# FPGA_RAM.net
KiCad netlist of a schematic drawn in Altium Designer
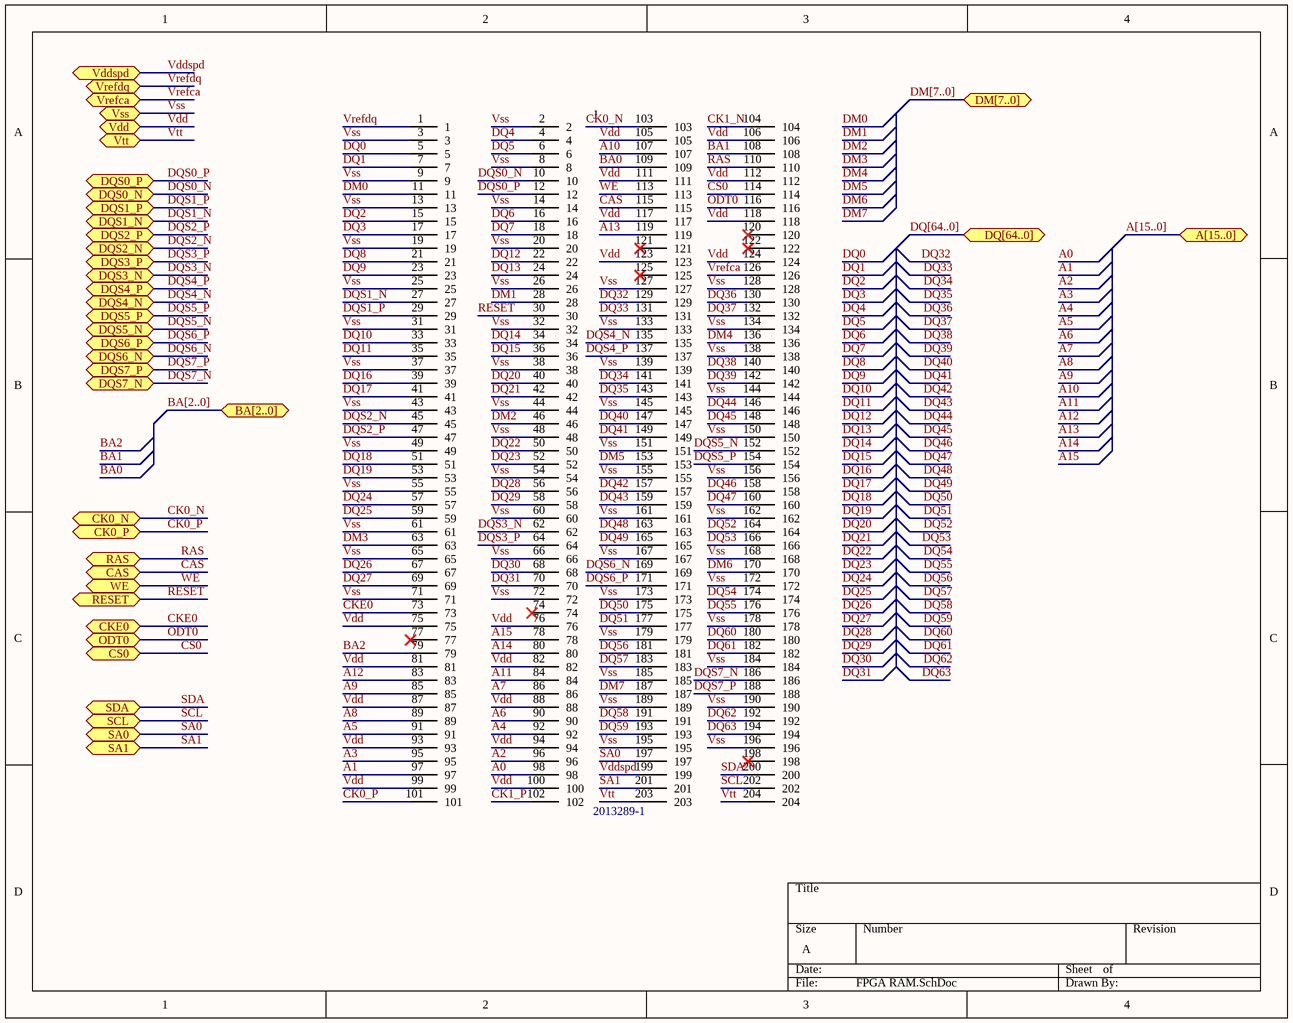
[diagram p0: FPGA RAM.SchDoc]

(export (version "E")
  (design (tool "Eeschema 10.0.6"))
  (components
    (comp (ref "J")
      (value "2013289-1")
      (footprint "2020-09-26_17-27-19:TE_2013289-1")
      (description "204 Position 0.6 mm Pitch Right Angle Surface Mount Socket DIMM Connector")
      (fields (field (name "DIGI-KEY_PART_NUMBER") "A115021-ND") (field (name "MF") "TE Connectivity"))
      (libsource (lib "2020-09-26_17-27-19") (part "2013289-1"))
    )
  )
  (nets
    (net (code "2") (name "/A0") (class "Default")
      (node (ref "J") (pin "98") (pinfunction "98_98") (pintype "passive"))
    )
    (net (code "3") (name "/A1") (class "Default")
      (node (ref "J") (pin "97") (pinfunction "97_97") (pintype "passive"))
    )
    (net (code "4") (name "/A2") (class "Default")
      (node (ref "J") (pin "96") (pinfunction "96_96") (pintype "passive"))
    )
    (net (code "5") (name "/A3") (class "Default")
      (node (ref "J") (pin "95") (pinfunction "95_95") (pintype "passive"))
    )
    (net (code "6") (name "/A4") (class "Default")
      (node (ref "J") (pin "92") (pinfunction "92_92") (pintype "passive"))
    )
    (net (code "7") (name "/A5") (class "Default")
      (node (ref "J") (pin "91") (pinfunction "91_91") (pintype "passive"))
    )
    (net (code "8") (name "/A6") (class "Default")
      (node (ref "J") (pin "90") (pinfunction "90_90") (pintype "passive"))
    )
    (net (code "9") (name "/A7") (class "Default")
      (node (ref "J") (pin "86") (pinfunction "86_86") (pintype "passive"))
    )
    (net (code "10") (name "/A8") (class "Default")
      (node (ref "J") (pin "89") (pinfunction "89_89") (pintype "passive"))
    )
    (net (code "11") (name "/A9") (class "Default")
      (node (ref "J") (pin "85") (pinfunction "85_85") (pintype "passive"))
    )
    (net (code "12") (name "/A10") (class "Default")
      (node (ref "J") (pin "107") (pinfunction "107_107") (pintype "passive"))
    )
    (net (code "13") (name "/A11") (class "Default")
      (node (ref "J") (pin "84") (pinfunction "84_84") (pintype "passive"))
    )
    (net (code "14") (name "/A12") (class "Default")
      (node (ref "J") (pin "83") (pinfunction "83_83") (pintype "passive"))
    )
    (net (code "15") (name "/A13") (class "Default")
      (node (ref "J") (pin "119") (pinfunction "119_119") (pintype "passive"))
    )
    (net (code "16") (name "/A14") (class "Default")
      (node (ref "J") (pin "80") (pinfunction "80_80") (pintype "passive"))
    )
    (net (code "17") (name "/A15") (class "Default")
      (node (ref "J") (pin "78") (pinfunction "78_78") (pintype "passive"))
    )
    (net (code "19") (name "/BA0") (class "Default")
      (node (ref "J") (pin "109") (pinfunction "109_109") (pintype "passive"))
    )
    (net (code "20") (name "/BA1") (class "Default")
      (node (ref "J") (pin "108") (pinfunction "108_108") (pintype "passive"))
    )
    (net (code "21") (name "/BA2") (class "Default")
      (node (ref "J") (pin "79") (pinfunction "79_79") (pintype "passive"))
    )
    (net (code "23") (name "/CAS") (class "Default")
      (node (ref "J") (pin "115") (pinfunction "115_115") (pintype "passive"))
    )
    (net (code "24") (name "/CK0_N") (class "Default")
      (node (ref "J") (pin "103") (pinfunction "103_103") (pintype "passive"))
    )
    (net (code "25") (name "/CK0_P") (class "Default")
      (node (ref "J") (pin "101") (pinfunction "101_101") (pintype "passive"))
    )
    (net (code "26") (name "/CK1_N") (class "Default")
      (node (ref "J") (pin "104") (pinfunction "104_104") (pintype "passive"))
    )
    (net (code "27") (name "/CK1_P") (class "Default")
      (node (ref "J") (pin "102") (pinfunction "102_102") (pintype "passive"))
    )
    (net (code "28") (name "/CKE0") (class "Default")
      (node (ref "J") (pin "73") (pinfunction "73_73") (pintype "passive"))
    )
    (net (code "29") (name "/CS0") (class "Default")
      (node (ref "J") (pin "114") (pinfunction "114_114") (pintype "passive"))
    )
    (net (code "30") (name "/DM0") (class "Default")
      (node (ref "J") (pin "11") (pinfunction "11_11") (pintype "passive"))
    )
    (net (code "31") (name "/DM1") (class "Default")
      (node (ref "J") (pin "28") (pinfunction "28_28") (pintype "passive"))
    )
    (net (code "32") (name "/DM2") (class "Default")
      (node (ref "J") (pin "46") (pinfunction "46_46") (pintype "passive"))
    )
    (net (code "33") (name "/DM3") (class "Default")
      (node (ref "J") (pin "63") (pinfunction "63_63") (pintype "passive"))
    )
    (net (code "34") (name "/DM4") (class "Default")
      (node (ref "J") (pin "136") (pinfunction "136_136") (pintype "passive"))
    )
    (net (code "35") (name "/DM5") (class "Default")
      (node (ref "J") (pin "153") (pinfunction "153_153") (pintype "passive"))
    )
    (net (code "36") (name "/DM6") (class "Default")
      (node (ref "J") (pin "170") (pinfunction "170_170") (pintype "passive"))
    )
    (net (code "37") (name "/DM7") (class "Default")
      (node (ref "J") (pin "187") (pinfunction "187_187") (pintype "passive"))
    )
    (net (code "39") (name "/DQ0") (class "Default")
      (node (ref "J") (pin "5") (pinfunction "5_5") (pintype "passive"))
    )
    (net (code "40") (name "/DQ1") (class "Default")
      (node (ref "J") (pin "7") (pinfunction "7_7") (pintype "passive"))
    )
    (net (code "41") (name "/DQ2") (class "Default")
      (node (ref "J") (pin "15") (pinfunction "15_15") (pintype "passive"))
    )
    (net (code "42") (name "/DQ3") (class "Default")
      (node (ref "J") (pin "17") (pinfunction "17_17") (pintype "passive"))
    )
    (net (code "43") (name "/DQ4") (class "Default")
      (node (ref "J") (pin "4") (pinfunction "4_4") (pintype "passive"))
    )
    (net (code "44") (name "/DQ5") (class "Default")
      (node (ref "J") (pin "6") (pinfunction "6_6") (pintype "passive"))
    )
    (net (code "45") (name "/DQ6") (class "Default")
      (node (ref "J") (pin "16") (pinfunction "16_16") (pintype "passive"))
    )
    (net (code "46") (name "/DQ7") (class "Default")
      (node (ref "J") (pin "18") (pinfunction "18_18") (pintype "passive"))
    )
    (net (code "47") (name "/DQ8") (class "Default")
      (node (ref "J") (pin "21") (pinfunction "21_21") (pintype "passive"))
    )
    (net (code "48") (name "/DQ9") (class "Default")
      (node (ref "J") (pin "23") (pinfunction "23_23") (pintype "passive"))
    )
    (net (code "49") (name "/DQ10") (class "Default")
      (node (ref "J") (pin "33") (pinfunction "33_33") (pintype "passive"))
    )
    (net (code "50") (name "/DQ11") (class "Default")
      (node (ref "J") (pin "35") (pinfunction "35_35") (pintype "passive"))
    )
    (net (code "51") (name "/DQ12") (class "Default")
      (node (ref "J") (pin "22") (pinfunction "22_22") (pintype "passive"))
    )
    (net (code "52") (name "/DQ13") (class "Default")
      (node (ref "J") (pin "24") (pinfunction "24_24") (pintype "passive"))
    )
    (net (code "53") (name "/DQ14") (class "Default")
      (node (ref "J") (pin "34") (pinfunction "34_34") (pintype "passive"))
    )
    (net (code "54") (name "/DQ15") (class "Default")
      (node (ref "J") (pin "36") (pinfunction "36_36") (pintype "passive"))
    )
    (net (code "55") (name "/DQ16") (class "Default")
      (node (ref "J") (pin "39") (pinfunction "39_39") (pintype "passive"))
    )
    (net (code "56") (name "/DQ17") (class "Default")
      (node (ref "J") (pin "41") (pinfunction "41_41") (pintype "passive"))
    )
    (net (code "57") (name "/DQ18") (class "Default")
      (node (ref "J") (pin "51") (pinfunction "51_51") (pintype "passive"))
    )
    (net (code "58") (name "/DQ19") (class "Default")
      (node (ref "J") (pin "53") (pinfunction "53_53") (pintype "passive"))
    )
    (net (code "59") (name "/DQ20") (class "Default")
      (node (ref "J") (pin "40") (pinfunction "40_40") (pintype "passive"))
    )
    (net (code "60") (name "/DQ21") (class "Default")
      (node (ref "J") (pin "42") (pinfunction "42_42") (pintype "passive"))
    )
    (net (code "61") (name "/DQ22") (class "Default")
      (node (ref "J") (pin "50") (pinfunction "50_50") (pintype "passive"))
    )
    (net (code "62") (name "/DQ23") (class "Default")
      (node (ref "J") (pin "52") (pinfunction "52_52") (pintype "passive"))
    )
    (net (code "63") (name "/DQ24") (class "Default")
      (node (ref "J") (pin "57") (pinfunction "57_57") (pintype "passive"))
    )
    (net (code "64") (name "/DQ25") (class "Default")
      (node (ref "J") (pin "59") (pinfunction "59_59") (pintype "passive"))
    )
    (net (code "65") (name "/DQ26") (class "Default")
      (node (ref "J") (pin "67") (pinfunction "67_67") (pintype "passive"))
    )
    (net (code "66") (name "/DQ27") (class "Default")
      (node (ref "J") (pin "69") (pinfunction "69_69") (pintype "passive"))
    )
    (net (code "67") (name "/DQ28") (class "Default")
      (node (ref "J") (pin "56") (pinfunction "56_56") (pintype "passive"))
    )
    (net (code "68") (name "/DQ29") (class "Default")
      (node (ref "J") (pin "58") (pinfunction "58_58") (pintype "passive"))
    )
    (net (code "69") (name "/DQ30") (class "Default")
      (node (ref "J") (pin "68") (pinfunction "68_68") (pintype "passive"))
    )
    (net (code "70") (name "/DQ31") (class "Default")
      (node (ref "J") (pin "70") (pinfunction "70_70") (pintype "passive"))
    )
    (net (code "71") (name "/DQ32") (class "Default")
      (node (ref "J") (pin "129") (pinfunction "129_129") (pintype "passive"))
    )
    (net (code "72") (name "/DQ33") (class "Default")
      (node (ref "J") (pin "131") (pinfunction "131_131") (pintype "passive"))
    )
    (net (code "73") (name "/DQ34") (class "Default")
      (node (ref "J") (pin "141") (pinfunction "141_141") (pintype "passive"))
    )
    (net (code "74") (name "/DQ35") (class "Default")
      (node (ref "J") (pin "143") (pinfunction "143_143") (pintype "passive"))
    )
    (net (code "75") (name "/DQ36") (class "Default")
      (node (ref "J") (pin "130") (pinfunction "130_130") (pintype "passive"))
    )
    (net (code "76") (name "/DQ37") (class "Default")
      (node (ref "J") (pin "132") (pinfunction "132_132") (pintype "passive"))
    )
    (net (code "77") (name "/DQ38") (class "Default")
      (node (ref "J") (pin "140") (pinfunction "140_140") (pintype "passive"))
    )
    (net (code "78") (name "/DQ39") (class "Default")
      (node (ref "J") (pin "142") (pinfunction "142_142") (pintype "passive"))
    )
    (net (code "79") (name "/DQ40") (class "Default")
      (node (ref "J") (pin "147") (pinfunction "147_147") (pintype "passive"))
    )
    (net (code "80") (name "/DQ41") (class "Default")
      (node (ref "J") (pin "149") (pinfunction "149_149") (pintype "passive"))
    )
    (net (code "81") (name "/DQ42") (class "Default")
      (node (ref "J") (pin "157") (pinfunction "157_157") (pintype "passive"))
    )
    (net (code "82") (name "/DQ43") (class "Default")
      (node (ref "J") (pin "159") (pinfunction "159_159") (pintype "passive"))
    )
    (net (code "83") (name "/DQ44") (class "Default")
      (node (ref "J") (pin "146") (pinfunction "146_146") (pintype "passive"))
    )
    (net (code "84") (name "/DQ45") (class "Default")
      (node (ref "J") (pin "148") (pinfunction "148_148") (pintype "passive"))
    )
    (net (code "85") (name "/DQ46") (class "Default")
      (node (ref "J") (pin "158") (pinfunction "158_158") (pintype "passive"))
    )
    (net (code "86") (name "/DQ47") (class "Default")
      (node (ref "J") (pin "160") (pinfunction "160_160") (pintype "passive"))
    )
    (net (code "87") (name "/DQ48") (class "Default")
      (node (ref "J") (pin "163") (pinfunction "163_163") (pintype "passive"))
    )
    (net (code "88") (name "/DQ49") (class "Default")
      (node (ref "J") (pin "165") (pinfunction "165_165") (pintype "passive"))
    )
    (net (code "89") (name "/DQ50") (class "Default")
      (node (ref "J") (pin "175") (pinfunction "175_175") (pintype "passive"))
    )
    (net (code "90") (name "/DQ51") (class "Default")
      (node (ref "J") (pin "177") (pinfunction "177_177") (pintype "passive"))
    )
    (net (code "91") (name "/DQ52") (class "Default")
      (node (ref "J") (pin "164") (pinfunction "164_164") (pintype "passive"))
    )
    (net (code "92") (name "/DQ53") (class "Default")
      (node (ref "J") (pin "166") (pinfunction "166_166") (pintype "passive"))
    )
    (net (code "93") (name "/DQ54") (class "Default")
      (node (ref "J") (pin "174") (pinfunction "174_174") (pintype "passive"))
    )
    (net (code "94") (name "/DQ55") (class "Default")
      (node (ref "J") (pin "176") (pinfunction "176_176") (pintype "passive"))
    )
    (net (code "95") (name "/DQ56") (class "Default")
      (node (ref "J") (pin "181") (pinfunction "181_181") (pintype "passive"))
    )
    (net (code "96") (name "/DQ57") (class "Default")
      (node (ref "J") (pin "183") (pinfunction "183_183") (pintype "passive"))
    )
    (net (code "97") (name "/DQ58") (class "Default")
      (node (ref "J") (pin "191") (pinfunction "191_191") (pintype "passive"))
    )
    (net (code "98") (name "/DQ59") (class "Default")
      (node (ref "J") (pin "193") (pinfunction "193_193") (pintype "passive"))
    )
    (net (code "99") (name "/DQ60") (class "Default")
      (node (ref "J") (pin "180") (pinfunction "180_180") (pintype "passive"))
    )
    (net (code "100") (name "/DQ61") (class "Default")
      (node (ref "J") (pin "182") (pinfunction "182_182") (pintype "passive"))
    )
    (net (code "101") (name "/DQ62") (class "Default")
      (node (ref "J") (pin "192") (pinfunction "192_192") (pintype "passive"))
    )
    (net (code "102") (name "/DQ63") (class "Default")
      (node (ref "J") (pin "194") (pinfunction "194_194") (pintype "passive"))
    )
    (net (code "103") (name "/DQS0_N") (class "Default")
      (node (ref "J") (pin "10") (pinfunction "10_10") (pintype "passive"))
    )
    (net (code "104") (name "/DQS0_P") (class "Default")
      (node (ref "J") (pin "12") (pinfunction "12_12") (pintype "passive"))
    )
    (net (code "105") (name "/DQS1_N") (class "Default")
      (node (ref "J") (pin "27") (pinfunction "27_27") (pintype "passive"))
    )
    (net (code "106") (name "/DQS1_P") (class "Default")
      (node (ref "J") (pin "29") (pinfunction "29_29") (pintype "passive"))
    )
    (net (code "107") (name "/DQS2_N") (class "Default")
      (node (ref "J") (pin "45") (pinfunction "45_45") (pintype "passive"))
    )
    (net (code "108") (name "/DQS2_P") (class "Default")
      (node (ref "J") (pin "47") (pinfunction "47_47") (pintype "passive"))
    )
    (net (code "109") (name "/DQS3_N") (class "Default")
      (node (ref "J") (pin "62") (pinfunction "62_62") (pintype "passive"))
    )
    (net (code "110") (name "/DQS3_P") (class "Default")
      (node (ref "J") (pin "64") (pinfunction "64_64") (pintype "passive"))
    )
    (net (code "111") (name "/DQS4_N") (class "Default")
      (node (ref "J") (pin "135") (pinfunction "135_135") (pintype "passive"))
    )
    (net (code "112") (name "/DQS4_P") (class "Default")
      (node (ref "J") (pin "137") (pinfunction "137_137") (pintype "passive"))
    )
    (net (code "113") (name "/DQS5_N") (class "Default")
      (node (ref "J") (pin "152") (pinfunction "152_152") (pintype "passive"))
    )
    (net (code "114") (name "/DQS5_P") (class "Default")
      (node (ref "J") (pin "154") (pinfunction "154_154") (pintype "passive"))
    )
    (net (code "115") (name "/DQS6_N") (class "Default")
      (node (ref "J") (pin "169") (pinfunction "169_169") (pintype "passive"))
    )
    (net (code "116") (name "/DQS6_P") (class "Default")
      (node (ref "J") (pin "171") (pinfunction "171_171") (pintype "passive"))
    )
    (net (code "117") (name "/DQS7_N") (class "Default")
      (node (ref "J") (pin "186") (pinfunction "186_186") (pintype "passive"))
    )
    (net (code "118") (name "/DQS7_P") (class "Default")
      (node (ref "J") (pin "188") (pinfunction "188_188") (pintype "passive"))
    )
    (net (code "120") (name "/ODT0") (class "Default")
      (node (ref "J") (pin "116") (pinfunction "116_116") (pintype "passive"))
    )
    (net (code "121") (name "/RAS") (class "Default")
      (node (ref "J") (pin "110") (pinfunction "110_110") (pintype "passive"))
    )
    (net (code "122") (name "/RESET") (class "Default")
      (node (ref "J") (pin "30") (pinfunction "30_30") (pintype "passive"))
    )
    (net (code "123") (name "/SA0") (class "Default")
      (node (ref "J") (pin "197") (pinfunction "197_197") (pintype "passive"))
    )
    (net (code "124") (name "/SA1") (class "Default")
      (node (ref "J") (pin "201") (pinfunction "201_201") (pintype "passive"))
    )
    (net (code "125") (name "/SCL") (class "Default")
      (node (ref "J") (pin "202") (pinfunction "202_202") (pintype "passive"))
    )
    (net (code "126") (name "/SDA") (class "Default")
      (node (ref "J") (pin "200") (pinfunction "200_200") (pintype "passive"))
    )
    (net (code "127") (name "/Vdd") (class "Default")
      (node (ref "J") (pin "100") (pinfunction "100_100") (pintype "passive"))
      (node (ref "J") (pin "105") (pinfunction "105_105") (pintype "passive"))
      (node (ref "J") (pin "106") (pinfunction "106_106") (pintype "passive"))
      (node (ref "J") (pin "111") (pinfunction "111_111") (pintype "passive"))
      (node (ref "J") (pin "112") (pinfunction "112_112") (pintype "passive"))
      (node (ref "J") (pin "117") (pinfunction "117_117") (pintype "passive"))
      (node (ref "J") (pin "118") (pinfunction "118_118") (pintype "passive"))
      (node (ref "J") (pin "123") (pinfunction "123_123") (pintype "passive"))
      (node (ref "J") (pin "124") (pinfunction "124_124") (pintype "passive"))
      (node (ref "J") (pin "75") (pinfunction "75_75") (pintype "passive"))
      (node (ref "J") (pin "76") (pinfunction "76_76") (pintype "passive"))
      (node (ref "J") (pin "81") (pinfunction "81_81") (pintype "passive"))
      (node (ref "J") (pin "82") (pinfunction "82_82") (pintype "passive"))
      (node (ref "J") (pin "87") (pinfunction "87_87") (pintype "passive"))
      (node (ref "J") (pin "88") (pinfunction "88_88") (pintype "passive"))
      (node (ref "J") (pin "93") (pinfunction "93_93") (pintype "passive"))
      (node (ref "J") (pin "94") (pinfunction "94_94") (pintype "passive"))
      (node (ref "J") (pin "99") (pinfunction "99_99") (pintype "passive"))
    )
    (net (code "128") (name "/Vddspd") (class "Default")
      (node (ref "J") (pin "199") (pinfunction "199_199") (pintype "passive"))
    )
    (net (code "129") (name "/Vrefca") (class "Default")
      (node (ref "J") (pin "126") (pinfunction "126_126") (pintype "passive"))
    )
    (net (code "130") (name "/Vrefdq") (class "Default")
      (node (ref "J") (pin "1") (pinfunction "1_1") (pintype "passive"))
    )
    (net (code "131") (name "/Vss") (class "Default")
      (node (ref "J") (pin "127") (pinfunction "127_127") (pintype "passive"))
      (node (ref "J") (pin "128") (pinfunction "128_128") (pintype "passive"))
      (node (ref "J") (pin "13") (pinfunction "13_13") (pintype "passive"))
      (node (ref "J") (pin "133") (pinfunction "133_133") (pintype "passive"))
      (node (ref "J") (pin "134") (pinfunction "134_134") (pintype "passive"))
      (node (ref "J") (pin "138") (pinfunction "138_138") (pintype "passive"))
      (node (ref "J") (pin "139") (pinfunction "139_139") (pintype "passive"))
      (node (ref "J") (pin "14") (pinfunction "14_14") (pintype "passive"))
      (node (ref "J") (pin "144") (pinfunction "144_144") (pintype "passive"))
      (node (ref "J") (pin "145") (pinfunction "145_145") (pintype "passive"))
      (node (ref "J") (pin "150") (pinfunction "150_150") (pintype "passive"))
      (node (ref "J") (pin "151") (pinfunction "151_151") (pintype "passive"))
      (node (ref "J") (pin "155") (pinfunction "155_155") (pintype "passive"))
      (node (ref "J") (pin "156") (pinfunction "156_156") (pintype "passive"))
      (node (ref "J") (pin "161") (pinfunction "161_161") (pintype "passive"))
      (node (ref "J") (pin "162") (pinfunction "162_162") (pintype "passive"))
      (node (ref "J") (pin "167") (pinfunction "167_167") (pintype "passive"))
      (node (ref "J") (pin "168") (pinfunction "168_168") (pintype "passive"))
      (node (ref "J") (pin "172") (pinfunction "172_172") (pintype "passive"))
      (node (ref "J") (pin "173") (pinfunction "173_173") (pintype "passive"))
      (node (ref "J") (pin "178") (pinfunction "178_178") (pintype "passive"))
      (node (ref "J") (pin "179") (pinfunction "179_179") (pintype "passive"))
      (node (ref "J") (pin "184") (pinfunction "184_184") (pintype "passive"))
      (node (ref "J") (pin "185") (pinfunction "185_185") (pintype "passive"))
      (node (ref "J") (pin "189") (pinfunction "189_189") (pintype "passive"))
      (node (ref "J") (pin "19") (pinfunction "19_19") (pintype "passive"))
      (node (ref "J") (pin "190") (pinfunction "190_190") (pintype "passive"))
      (node (ref "J") (pin "195") (pinfunction "195_195") (pintype "passive"))
      (node (ref "J") (pin "196") (pinfunction "196_196") (pintype "passive"))
      (node (ref "J") (pin "2") (pinfunction "2_2") (pintype "passive"))
      (node (ref "J") (pin "20") (pinfunction "20_20") (pintype "passive"))
      (node (ref "J") (pin "25") (pinfunction "25_25") (pintype "passive"))
      (node (ref "J") (pin "26") (pinfunction "26_26") (pintype "passive"))
      (node (ref "J") (pin "3") (pinfunction "3_3") (pintype "passive"))
      (node (ref "J") (pin "31") (pinfunction "31_31") (pintype "passive"))
      (node (ref "J") (pin "32") (pinfunction "32_32") (pintype "passive"))
      (node (ref "J") (pin "37") (pinfunction "37_37") (pintype "passive"))
      (node (ref "J") (pin "38") (pinfunction "38_38") (pintype "passive"))
      (node (ref "J") (pin "43") (pinfunction "43_43") (pintype "passive"))
      (node (ref "J") (pin "44") (pinfunction "44_44") (pintype "passive"))
      (node (ref "J") (pin "48") (pinfunction "48_48") (pintype "passive"))
      (node (ref "J") (pin "49") (pinfunction "49_49") (pintype "passive"))
      (node (ref "J") (pin "54") (pinfunction "54_54") (pintype "passive"))
      (node (ref "J") (pin "55") (pinfunction "55_55") (pintype "passive"))
      (node (ref "J") (pin "60") (pinfunction "60_60") (pintype "passive"))
      (node (ref "J") (pin "61") (pinfunction "61_61") (pintype "passive"))
      (node (ref "J") (pin "65") (pinfunction "65_65") (pintype "passive"))
      (node (ref "J") (pin "66") (pinfunction "66_66") (pintype "passive"))
      (node (ref "J") (pin "71") (pinfunction "71_71") (pintype "passive"))
      (node (ref "J") (pin "72") (pinfunction "72_72") (pintype "passive"))
      (node (ref "J") (pin "8") (pinfunction "8_8") (pintype "passive"))
      (node (ref "J") (pin "9") (pinfunction "9_9") (pintype "passive"))
    )
    (net (code "132") (name "/Vtt") (class "Default")
      (node (ref "J") (pin "203") (pinfunction "203_203") (pintype "passive"))
      (node (ref "J") (pin "204") (pinfunction "204_204") (pintype "passive"))
    )
    (net (code "133") (name "/WE") (class "Default")
      (node (ref "J") (pin "113") (pinfunction "113_113") (pintype "passive"))
    )
    (net (code "134") (name "unconnected-(J-Pad74)") (class "Default")
      (node (ref "J") (pin "74") (pinfunction "74_74") (pintype "passive+no_connect"))
    )
    (net (code "135") (name "unconnected-(J-Pad77)") (class "Default")
      (node (ref "J") (pin "77") (pinfunction "77_77") (pintype "passive+no_connect"))
    )
    (net (code "136") (name "unconnected-(J-Pad120)") (class "Default")
      (node (ref "J") (pin "120") (pinfunction "120_120") (pintype "passive+no_connect"))
    )
    (net (code "137") (name "unconnected-(J-Pad121)") (class "Default")
      (node (ref "J") (pin "121") (pinfunction "121_121") (pintype "passive+no_connect"))
    )
    (net (code "138") (name "unconnected-(J-Pad122)") (class "Default")
      (node (ref "J") (pin "122") (pinfunction "122_122") (pintype "passive+no_connect"))
    )
    (net (code "139") (name "unconnected-(J-Pad125)") (class "Default")
      (node (ref "J") (pin "125") (pinfunction "125_125") (pintype "passive+no_connect"))
    )
    (net (code "140") (name "unconnected-(J-Pad198)") (class "Default")
      (node (ref "J") (pin "198") (pinfunction "198_198") (pintype "passive+no_connect"))
    )
  )
)
